# lab2.net
KiCad netlist of a schematic drawn in EAGLE
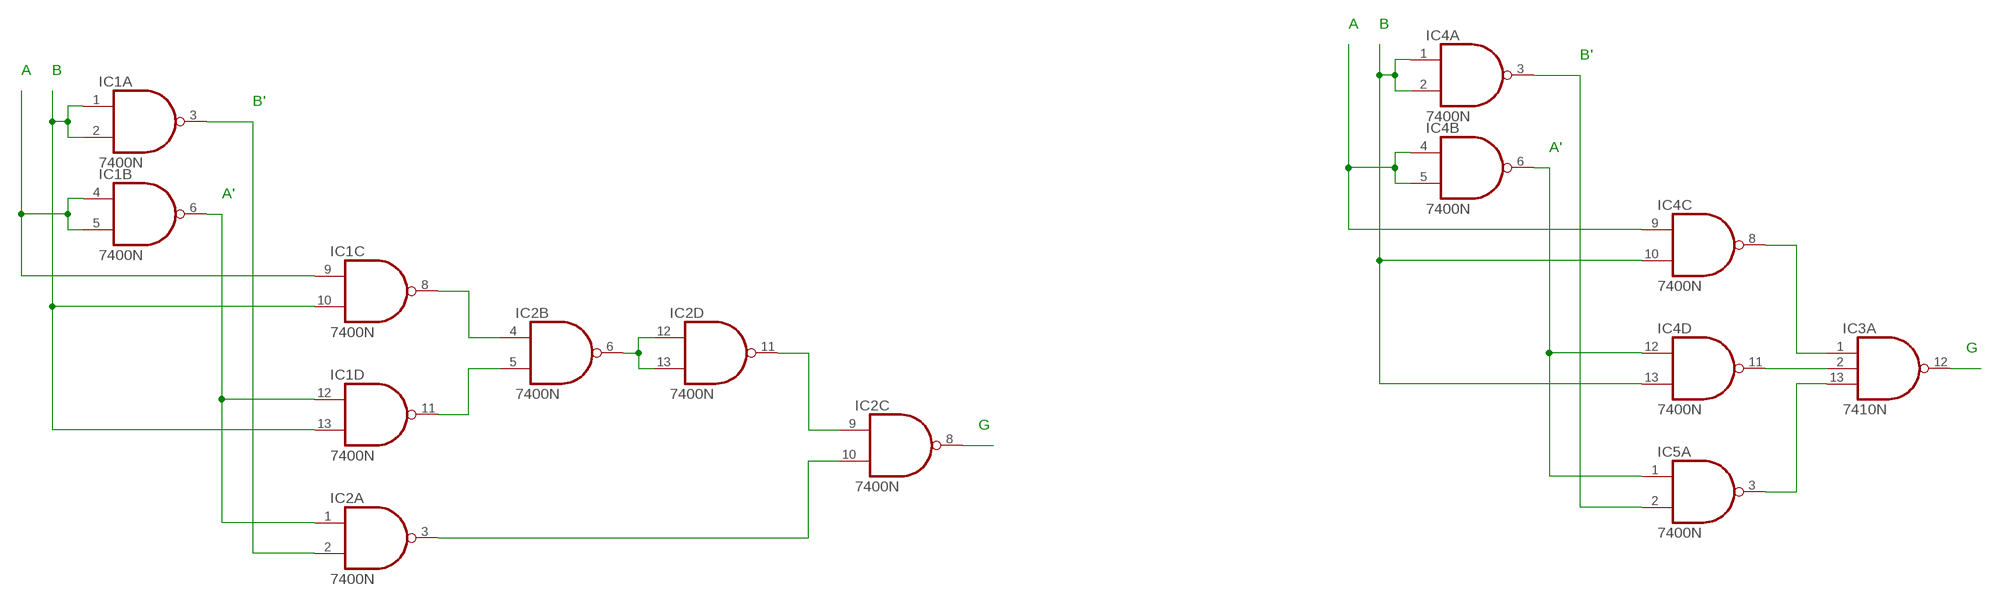
[diagram p0: schematic, sheet 1]

(export (version "E")
  (design (tool "Eeschema 10.0.6"))
  (components
    (comp (ref "IC1")
      (value "7400N")
      (footprint "eagle-import:DIL14")
      (libsource (lib "eagle-import") (part "7400N"))
    )
    (comp (ref "IC2")
      (value "7400N")
      (footprint "eagle-import:DIL14")
      (libsource (lib "eagle-import") (part "7400N"))
    )
    (comp (ref "IC3")
      (value "7410N")
      (footprint "eagle-import:DIL14")
      (libsource (lib "eagle-import") (part "7410N"))
    )
    (comp (ref "IC4")
      (value "7400N")
      (footprint "eagle-import:DIL14")
      (libsource (lib "eagle-import") (part "7400N"))
    )
    (comp (ref "IC5")
      (value "7400N")
      (footprint "eagle-import:DIL14")
      (libsource (lib "eagle-import") (part "7400N"))
    )
  )
  (nets
    (net (code "1") (name "Net-(IC1A-I0)") (class "Default")
      (node (ref "IC1") (pin "1") (pinfunction "I0_1") (pintype "input"))
      (node (ref "IC1") (pin "10") (pinfunction "I1_10") (pintype "input"))
      (node (ref "IC1") (pin "13") (pinfunction "I1_13") (pintype "input"))
      (node (ref "IC1") (pin "2") (pinfunction "I1_2") (pintype "input"))
    )
    (net (code "2") (name "Net-(IC1A-O)") (class "Default")
      (node (ref "IC1") (pin "3") (pinfunction "O_3") (pintype "output"))
      (node (ref "IC2") (pin "2") (pinfunction "I1_2") (pintype "input"))
    )
    (net (code "3") (name "Net-(IC1B-I0)") (class "Default")
      (node (ref "IC1") (pin "4") (pinfunction "I0_4") (pintype "input"))
      (node (ref "IC1") (pin "5") (pinfunction "I1_5") (pintype "input"))
      (node (ref "IC1") (pin "9") (pinfunction "I0_9") (pintype "input"))
    )
    (net (code "4") (name "Net-(IC1B-O)") (class "Default")
      (node (ref "IC1") (pin "12") (pinfunction "I0_12") (pintype "input"))
      (node (ref "IC1") (pin "6") (pinfunction "O_6") (pintype "output"))
      (node (ref "IC2") (pin "1") (pinfunction "I0_1") (pintype "input"))
    )
    (net (code "5") (name "Net-(IC1C-O)") (class "Default")
      (node (ref "IC1") (pin "8") (pinfunction "O_8") (pintype "output"))
      (node (ref "IC2") (pin "4") (pinfunction "I0_4") (pintype "input"))
    )
    (net (code "6") (name "Net-(IC1D-O)") (class "Default")
      (node (ref "IC1") (pin "11") (pinfunction "O_11") (pintype "output"))
      (node (ref "IC2") (pin "5") (pinfunction "I1_5") (pintype "input"))
    )
    (net (code "7") (name "Net-(IC2A-O)") (class "Default")
      (node (ref "IC2") (pin "10") (pinfunction "I1_10") (pintype "input"))
      (node (ref "IC2") (pin "3") (pinfunction "O_3") (pintype "output"))
    )
    (net (code "8") (name "Net-(IC2B-O)") (class "Default")
      (node (ref "IC2") (pin "12") (pinfunction "I0_12") (pintype "input"))
      (node (ref "IC2") (pin "13") (pinfunction "I1_13") (pintype "input"))
      (node (ref "IC2") (pin "6") (pinfunction "O_6") (pintype "output"))
    )
    (net (code "9") (name "Net-(IC2C-I0)") (class "Default")
      (node (ref "IC2") (pin "11") (pinfunction "O_11") (pintype "output"))
      (node (ref "IC2") (pin "9") (pinfunction "I0_9") (pintype "input"))
    )
    (net (code "10") (name "Net-(IC3A-I0)") (class "Default")
      (node (ref "IC3") (pin "1") (pinfunction "I0_1") (pintype "input"))
      (node (ref "IC4") (pin "8") (pinfunction "O_8") (pintype "output"))
    )
    (net (code "11") (name "Net-(IC3A-I1)") (class "Default")
      (node (ref "IC3") (pin "2") (pinfunction "I1_2") (pintype "input"))
      (node (ref "IC4") (pin "11") (pinfunction "O_11") (pintype "output"))
    )
    (net (code "12") (name "Net-(IC3A-I2)") (class "Default")
      (node (ref "IC3") (pin "13") (pinfunction "I2_13") (pintype "input"))
      (node (ref "IC5") (pin "3") (pinfunction "O_3") (pintype "output"))
    )
    (net (code "13") (name "Net-(IC4A-I0)") (class "Default")
      (node (ref "IC4") (pin "1") (pinfunction "I0_1") (pintype "input"))
      (node (ref "IC4") (pin "10") (pinfunction "I1_10") (pintype "input"))
      (node (ref "IC4") (pin "13") (pinfunction "I1_13") (pintype "input"))
      (node (ref "IC4") (pin "2") (pinfunction "I1_2") (pintype "input"))
    )
    (net (code "14") (name "Net-(IC4A-O)") (class "Default")
      (node (ref "IC4") (pin "3") (pinfunction "O_3") (pintype "output"))
      (node (ref "IC5") (pin "2") (pinfunction "I1_2") (pintype "input"))
    )
    (net (code "15") (name "Net-(IC4B-I0)") (class "Default")
      (node (ref "IC4") (pin "4") (pinfunction "I0_4") (pintype "input"))
      (node (ref "IC4") (pin "5") (pinfunction "I1_5") (pintype "input"))
      (node (ref "IC4") (pin "9") (pinfunction "I0_9") (pintype "input"))
    )
    (net (code "16") (name "Net-(IC4B-O)") (class "Default")
      (node (ref "IC4") (pin "12") (pinfunction "I0_12") (pintype "input"))
      (node (ref "IC4") (pin "6") (pinfunction "O_6") (pintype "output"))
      (node (ref "IC5") (pin "1") (pinfunction "I0_1") (pintype "input"))
    )
    (net (code "17") (name "unconnected-(IC2C-O-Pad8)") (class "Default")
      (node (ref "IC2") (pin "8") (pinfunction "O_8") (pintype "output"))
    )
    (net (code "18") (name "unconnected-(IC3A-O-Pad12)") (class "Default")
      (node (ref "IC3") (pin "12") (pinfunction "O_12") (pintype "output"))
    )
  )
)
